# Power.net
KiCad netlist of a schematic drawn in Altium Designer
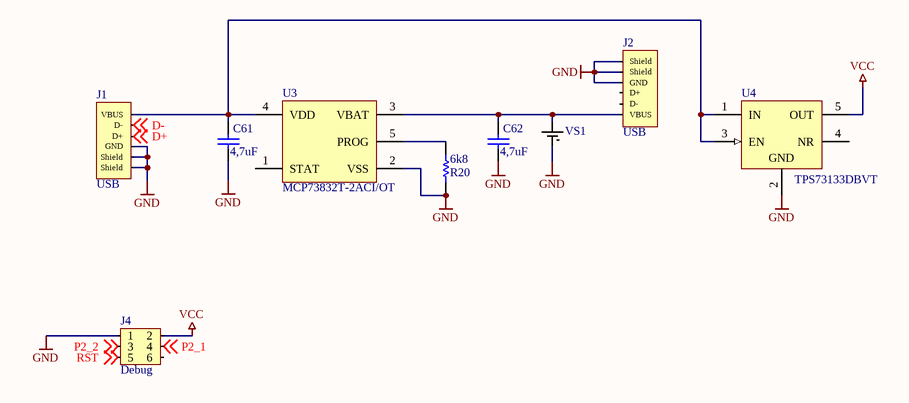
[diagram p0: Power.SchDoc]

(export (version "E")
  (design (tool "Eeschema 10.0.6"))
  (components
    (comp (ref "C61")
      (value "4,7uF")
      (footprint "CAPC0402(1005)60_L")
      (description "CAP 10pF 10V ±0.25pF 0402 (1005 Metric) Thickness 0.6mm SMD")
      (fields (field (name "TOLERANCE") "±0.25pF"))
      (libsource (lib "Altium Content Vault") (part "CMP-1034-00698-1"))
    )
    (comp (ref "C62")
      (value "4,7uF")
      (footprint "CAPC0402(1005)60_L")
      (description "CAP 10pF 10V ±0.25pF 0402 (1005 Metric) Thickness 0.6mm SMD")
      (fields (field (name "TOLERANCE") "±0.25pF"))
      (libsource (lib "Altium Content Vault") (part "CMP-1034-00698-1"))
    )
    (comp (ref "J1") (value "USB") (footprint "USB") (libsource (lib "Schlib1") (part "USB")))
    (comp (ref "J2") (value "USB") (footprint "USB") (libsource (lib "") (part "USB_1")))
    (comp (ref "J4") (value "Debug") (footprint "DEBUG") (libsource (lib "Schlib1") (part "Debug")))
    (comp (ref "R20")
      (value "6k8")
      (footprint "RESC0402(1005)_M")
      (description "6K8 0.063W 5% 0402 (1005 Metric)  SMD")
      (fields (field (name "POWER") "0.063 W") (field (name "TOLERANCE") "5 %"))
      (libsource (lib "Altium Content Vault") (part "CMP-1011-00094-1"))
    )
    (comp (ref "U3")
      (value "MCP73832T-2ACI/OT")
      (footprint "SOT-23-OT5_M")
      (libsource (lib "Altium Content Vault") (part "CMP-0133-00138-1"))
    )
    (comp (ref "U4")
      (value "TPS73133DBVT")
      (footprint "TI-DBV5_M")
      (fields (field (name "MANUFACTURER") "Texas Instruments"))
      (libsource (lib "Altium Content Vault") (part "CMP-0394-00649-1"))
    )
    (comp (ref "VS1")
      (value "Battery")
      (footprint "Misscelaneous con")
      (libsource (lib "Schlib1") (part "Battery"))
    )
  )
  (nets
    (net (code "1") (name "D+") (class "Default")
      (node (ref "J1") (pin "2") (pinfunction "D+_2") (pintype "passive"))
    )
    (net (code "2") (name "D-") (class "Default")
      (node (ref "J1") (pin "1") (pinfunction "D-_1") (pintype "passive"))
    )
    (net (code "3") (name "GND") (class "Default")
      (node (ref "C61") (pin "2") (pinfunction "2_2") (pintype "passive"))
      (node (ref "C62") (pin "2") (pinfunction "2_2") (pintype "passive"))
      (node (ref "J1") (pin "3") (pinfunction "GND_3") (pintype "passive"))
      (node (ref "J1") (pin "4") (pinfunction "Shield_4") (pintype "passive"))
      (node (ref "J1") (pin "5") (pinfunction "Shield_5") (pintype "passive"))
      (node (ref "J2") (pin "3") (pinfunction "GND_3") (pintype "passive"))
      (node (ref "J2") (pin "4") (pinfunction "Shield_4") (pintype "passive"))
      (node (ref "J2") (pin "5") (pinfunction "Shield_5") (pintype "passive"))
      (node (ref "J4") (pin "1") (pinfunction "1_1") (pintype "passive"))
      (node (ref "R20") (pin "1") (pinfunction "1_1") (pintype "passive"))
      (node (ref "U3") (pin "2") (pinfunction "VSS_2") (pintype "power_in"))
      (node (ref "U4") (pin "2") (pinfunction "GND_2") (pintype "power_in"))
      (node (ref "VS1") (pin "1") (pinfunction "-_1") (pintype "passive"))
    )
    (net (code "4") (name "Net-(J1-VBUS)") (class "Default")
      (node (ref "C61") (pin "1") (pinfunction "1_1") (pintype "passive"))
      (node (ref "J1") (pin "0") (pinfunction "VBUS_0") (pintype "passive"))
      (node (ref "U3") (pin "4") (pinfunction "VDD_4") (pintype "power_in"))
      (node (ref "U4") (pin "1") (pinfunction "IN_1") (pintype "power_in"))
      (node (ref "U4") (pin "3") (pinfunction "EN_3") (pintype "input"))
    )
    (net (code "5") (name "Net-(J2-VBUS)") (class "Default")
      (node (ref "C62") (pin "1") (pinfunction "1_1") (pintype "passive"))
      (node (ref "J2") (pin "0") (pinfunction "VBUS_0") (pintype "passive"))
      (node (ref "U3") (pin "3") (pinfunction "VBAT_3") (pintype "power_in"))
      (node (ref "VS1") (pin "0") (pinfunction "+_0") (pintype "passive"))
    )
    (net (code "6") (name "Net-(U3-PROG)") (class "Default")
      (node (ref "R20") (pin "2") (pinfunction "2_2") (pintype "passive"))
      (node (ref "U3") (pin "5") (pinfunction "PROG_5") (pintype "passive"))
    )
    (net (code "7") (name "P2_1") (class "Default")
      (node (ref "J4") (pin "4") (pinfunction "4_4") (pintype "passive"))
    )
    (net (code "8") (name "P2_2") (class "Default")
      (node (ref "J4") (pin "3") (pinfunction "3_3") (pintype "passive"))
    )
    (net (code "9") (name "RST") (class "Default")
      (node (ref "J4") (pin "5") (pinfunction "5_5") (pintype "passive"))
    )
    (net (code "10") (name "VCC") (class "Default")
      (node (ref "J4") (pin "2") (pinfunction "2_2") (pintype "passive"))
      (node (ref "U4") (pin "5") (pinfunction "OUT_5") (pintype "power_in"))
    )
    (net (code "11") (name "unconnected-(J2-D+-Pad2)") (class "Default")
      (node (ref "J2") (pin "2") (pinfunction "D+_2") (pintype "passive"))
    )
    (net (code "12") (name "unconnected-(J2-D--Pad1)") (class "Default")
      (node (ref "J2") (pin "1") (pinfunction "D-_1") (pintype "passive"))
    )
    (net (code "13") (name "unconnected-(J4-Pad6)") (class "Default")
      (node (ref "J4") (pin "6") (pinfunction "6_6") (pintype "passive"))
    )
    (net (code "14") (name "unconnected-(U3-STAT-Pad1)") (class "Default")
      (node (ref "U3") (pin "1") (pinfunction "STAT_1") (pintype "open_collector"))
    )
    (net (code "15") (name "unconnected-(U4-NR-Pad4)") (class "Default")
      (node (ref "U4") (pin "4") (pinfunction "NR_4") (pintype "passive"))
    )
  )
)
